# Power_Supply_Section.net
KiCad netlist of a schematic drawn in Altium Designer
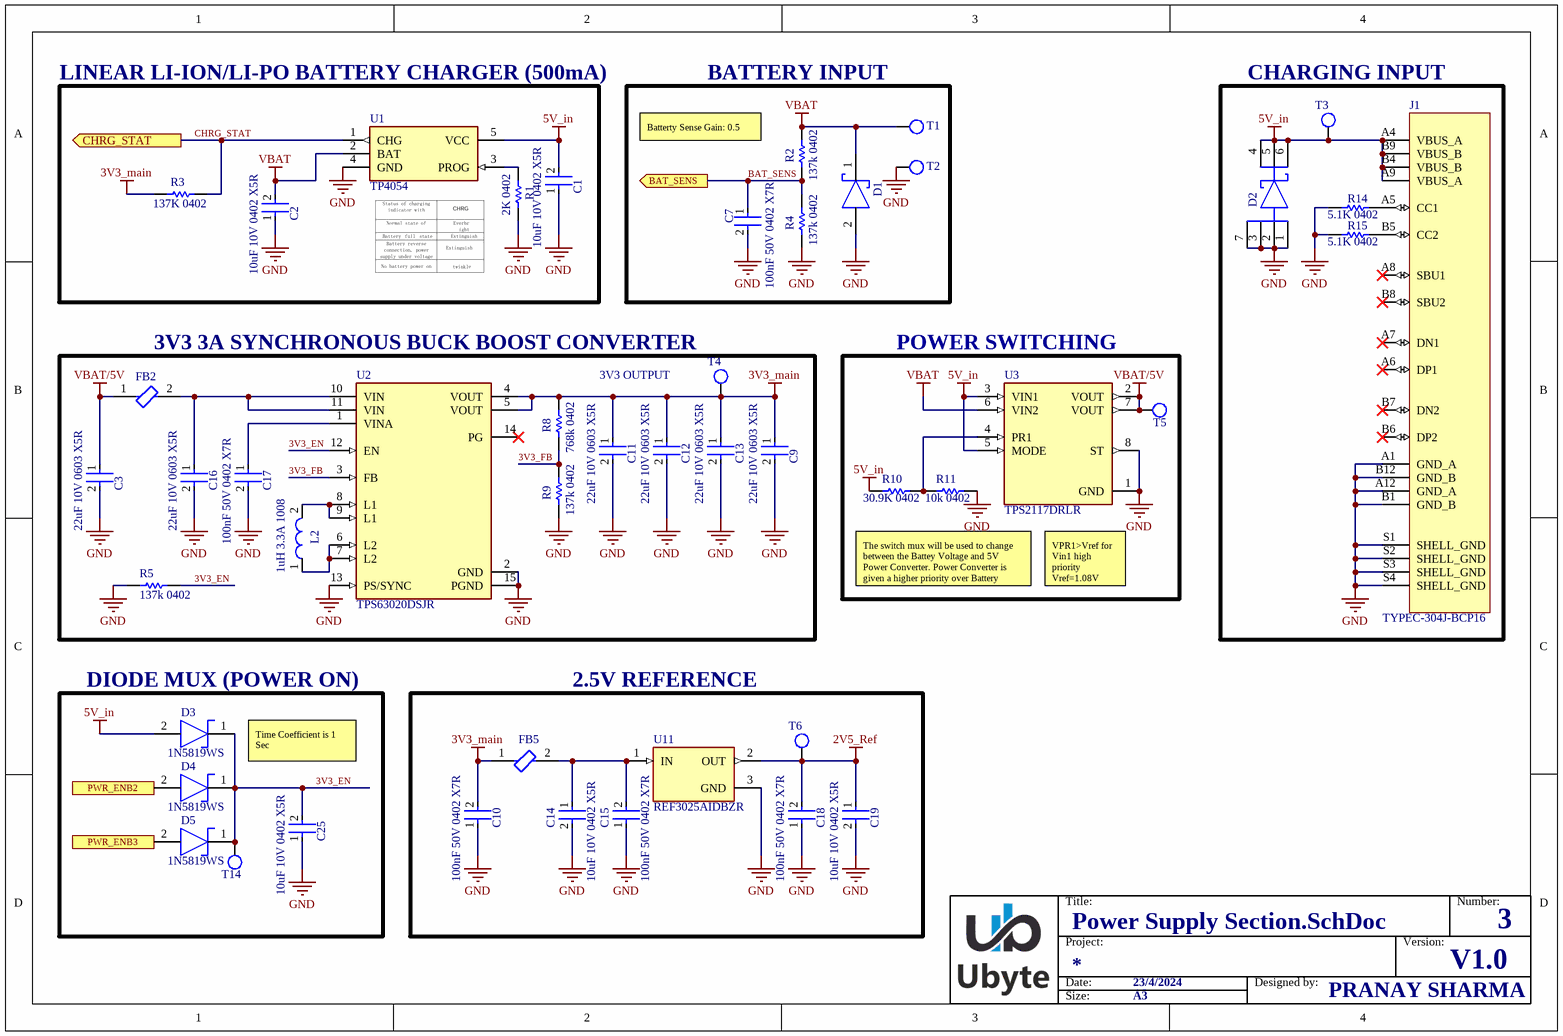
[diagram p0: Power Supply Section.SchDoc]

(export (version "E")
  (design (tool "Eeschema 10.0.6"))
  (components
    (comp (ref "C1")
      (value "10uF 10V 0402 X5R")
      (footprint "Res, Cap, Ind, LED, FB_Lib:0402 IPC CLASS C CAPACITOR")
      (libsource (lib "Capacitor_Lib") (part "10uF 10V 0402 X5R"))
    )
    (comp (ref "C2")
      (value "10uF 10V 0402 X5R")
      (footprint "Res, Cap, Ind, LED, FB_Lib:0402 IPC CLASS C CAPACITOR")
      (libsource (lib "Capacitor_Lib") (part "10uF 10V 0402 X5R"))
    )
    (comp (ref "C3")
      (value "22uF 10V 0603 X5R")
      (footprint "Res, Cap, Ind, LED, FB_Lib:0603 IPC CLASS C CAPACITOR")
      (libsource (lib "Capacitor_Lib") (part "22uF 10V 0603 X5R"))
    )
    (comp (ref "C7")
      (value "100nF 50V 0402 X7R")
      (footprint "Res, Cap, Ind, LED, FB_Lib:0402 IPC CLASS C CAPACITOR")
      (libsource (lib "Capacitor_Lib") (part "100nF 50V 0402 X7R"))
    )
    (comp (ref "C9")
      (value "22uF 10V 0603 X5R")
      (footprint "Res, Cap, Ind, LED, FB_Lib:0603 IPC CLASS C CAPACITOR")
      (libsource (lib "Capacitor_Lib") (part "22uF 10V 0603 X5R"))
    )
    (comp (ref "C10")
      (value "100nF 50V 0402 X7R")
      (footprint "Res, Cap, Ind, LED, FB_Lib:0402 IPC CLASS C CAPACITOR")
      (libsource (lib "Capacitor_Lib") (part "100nF 50V 0402 X7R"))
    )
    (comp (ref "C11")
      (value "22uF 10V 0603 X5R")
      (footprint "Res, Cap, Ind, LED, FB_Lib:0603 IPC CLASS C CAPACITOR")
      (libsource (lib "Capacitor_Lib") (part "22uF 10V 0603 X5R"))
    )
    (comp (ref "C12")
      (value "22uF 10V 0603 X5R")
      (footprint "Res, Cap, Ind, LED, FB_Lib:0603 IPC CLASS C CAPACITOR")
      (libsource (lib "Capacitor_Lib") (part "22uF 10V 0603 X5R"))
    )
    (comp (ref "C13")
      (value "22uF 10V 0603 X5R")
      (footprint "Res, Cap, Ind, LED, FB_Lib:0603 IPC CLASS C CAPACITOR")
      (libsource (lib "Capacitor_Lib") (part "22uF 10V 0603 X5R"))
    )
    (comp (ref "C14")
      (value "10uF 10V 0402 X5R")
      (footprint "Res, Cap, Ind, LED, FB_Lib:0402 IPC CLASS C CAPACITOR")
      (libsource (lib "Capacitor_Lib") (part "10uF 10V 0402 X5R"))
    )
    (comp (ref "C15")
      (value "100nF 50V 0402 X7R")
      (footprint "Res, Cap, Ind, LED, FB_Lib:0402 IPC CLASS C CAPACITOR")
      (libsource (lib "Capacitor_Lib") (part "100nF 50V 0402 X7R"))
    )
    (comp (ref "C16")
      (value "22uF 10V 0603 X5R")
      (footprint "Res, Cap, Ind, LED, FB_Lib:0603 IPC CLASS C CAPACITOR")
      (libsource (lib "Capacitor_Lib") (part "22uF 10V 0603 X5R"))
    )
    (comp (ref "C17")
      (value "100nF 50V 0402 X7R")
      (footprint "Res, Cap, Ind, LED, FB_Lib:0402 IPC CLASS C CAPACITOR")
      (libsource (lib "Capacitor_Lib") (part "100nF 50V 0402 X7R"))
    )
    (comp (ref "C18")
      (value "100nF 50V 0402 X7R")
      (footprint "Res, Cap, Ind, LED, FB_Lib:0402 IPC CLASS C CAPACITOR")
      (libsource (lib "Capacitor_Lib") (part "100nF 50V 0402 X7R"))
    )
    (comp (ref "C19")
      (value "10uF 10V 0402 X5R")
      (footprint "Res, Cap, Ind, LED, FB_Lib:0402 IPC CLASS C CAPACITOR")
      (libsource (lib "Capacitor_Lib") (part "10uF 10V 0402 X5R"))
    )
    (comp (ref "C25")
      (value "10uF 10V 0402 X5R")
      (footprint "Res, Cap, Ind, LED, FB_Lib:0402 IPC CLASS C CAPACITOR")
      (libsource (lib "Capacitor_Lib") (part "10uF 10V 0402 X5R"))
    )
    (comp (ref "D1")
      (value "SP3031-01ETG")
      (footprint "Res, Cap, Ind, LED, FB_Lib:SOD882 IPC-C")
      (libsource (lib "Diodes_Lib") (part "SP3031-01ETG"))
    )
    (comp (ref "D2")
      (value "TVS0500DRVR")
      (footprint "Res, Cap, Ind, LED, FB_Lib:DRV0006A IPC-C")
      (libsource (lib "Diodes_Lib") (part "TVS0500DRVR"))
    )
    (comp (ref "D3")
      (value "1N5819WS")
      (footprint "Res, Cap, Ind, LED, FB_Lib:SOD-323 IPC-C")
      (libsource (lib "Diodes_Lib") (part "1N5819WS"))
    )
    (comp (ref "D4")
      (value "1N5819WS")
      (footprint "Res, Cap, Ind, LED, FB_Lib:SOD-323 IPC-C")
      (libsource (lib "Diodes_Lib") (part "1N5819WS"))
    )
    (comp (ref "D5")
      (value "1N5819WS")
      (footprint "Res, Cap, Ind, LED, FB_Lib:SOD-323 IPC-C")
      (libsource (lib "Diodes_Lib") (part "1N5819WS"))
    )
    (comp (ref "FB2")
      (value "BLM21SP111SN1D")
      (footprint "Res, Cap, Ind, LED, FB_Lib:0603 IPC CLASS C FERRITE BEAD")
      (libsource (lib "Ferrite_Bead_Lib") (part "BLM21SP111SN1D"))
    )
    (comp (ref "FB5")
      (value "BLM15AX102SN1D")
      (footprint "Res, Cap, Ind, LED, FB_Lib:0402 IPC CLASS C FERRITE BEAD")
      (libsource (lib "Ferrite_Bead_Lib") (part "BLM15AX102SN1D"))
    )
    (comp (ref "J1")
      (value "TYPEC-304J-BCP16")
      (footprint "VALCON_CSP-USC16-TR")
      (libsource (lib "V1.0") (part "USB Type C"))
    )
    (comp (ref "L2")
      (value "1uH 3.3A 1008")
      (footprint "Res, Cap, Ind, LED, FB_Lib:1008 Inductor IPC-C")
      (libsource (lib "Inductor_Lib") (part "DFE252012F-1R0M=P2"))
    )
    (comp (ref "R1")
      (value "2K 0402")
      (footprint "Res, Cap, Ind, LED, FB_Lib:0402 IPC CLASS C RESISTOR")
      (libsource (lib "Resistor_Lib") (part "2K 1% 0402"))
    )
    (comp (ref "R2")
      (value "137k 0402")
      (footprint "Res, Cap, Ind, LED, FB_Lib:0402 IPC CLASS C RESISTOR")
      (libsource (lib "Resistor_Lib") (part "10k 1% 0402"))
    )
    (comp (ref "R3")
      (value "137K 0402")
      (footprint "Res, Cap, Ind, LED, FB_Lib:0402 IPC CLASS C RESISTOR")
      (libsource (lib "Resistor_Lib") (part "137K 1% 0402"))
    )
    (comp (ref "R4")
      (value "137k 0402")
      (footprint "Res, Cap, Ind, LED, FB_Lib:0402 IPC CLASS C RESISTOR")
      (libsource (lib "Resistor_Lib") (part "10k 1% 0402"))
    )
    (comp (ref "R5")
      (value "137k 0402")
      (footprint "Res, Cap, Ind, LED, FB_Lib:0402 IPC CLASS C RESISTOR")
      (libsource (lib "Resistor_Lib") (part "10k 1% 0402"))
    )
    (comp (ref "R8")
      (value "768k 0402")
      (footprint "Res, Cap, Ind, LED, FB_Lib:0402 IPC CLASS C RESISTOR")
      (libsource (lib "Resistor_Lib") (part "10k 1% 0402"))
    )
    (comp (ref "R9")
      (value "137k 0402")
      (footprint "Res, Cap, Ind, LED, FB_Lib:0402 IPC CLASS C RESISTOR")
      (libsource (lib "Resistor_Lib") (part "10k 1% 0402"))
    )
    (comp (ref "R10")
      (value "30.9K 0402")
      (footprint "Res, Cap, Ind, LED, FB_Lib:0402 IPC CLASS C RESISTOR")
      (libsource (lib "Resistor_Lib") (part "30.9K 1%  0402"))
    )
    (comp (ref "R11")
      (value "10k 0402")
      (footprint "Res, Cap, Ind, LED, FB_Lib:0402 IPC CLASS C RESISTOR")
      (libsource (lib "Resistor_Lib") (part "10k 1% 0402"))
    )
    (comp (ref "R14")
      (value "5.1K 0402")
      (footprint "Res, Cap, Ind, LED, FB_Lib:0402 IPC CLASS C RESISTOR")
      (libsource (lib "Resistor_Lib") (part "5.1K 1% 0402"))
    )
    (comp (ref "R15")
      (value "5.1K 0402")
      (footprint "Res, Cap, Ind, LED, FB_Lib:0402 IPC CLASS C RESISTOR")
      (libsource (lib "Resistor_Lib") (part "5.1K 1% 0402"))
    )
    (comp (ref "T1")
      (value "Test Point TH")
      (footprint "Miscellaneous_Lib:Test Point TH")
      (libsource (lib "Miscellaneous_Lib") (part "Test Point TH"))
    )
    (comp (ref "T2")
      (value "Test Point TH")
      (footprint "Miscellaneous_Lib:Test Point TH")
      (libsource (lib "Miscellaneous_Lib") (part "Test Point TH"))
    )
    (comp (ref "T3")
      (value "TP")
      (footprint "Miscellaneous_Lib:Testpoint1")
      (libsource (lib "Miscellaneous_Lib") (part "Testpoint1"))
    )
    (comp (ref "T4")
      (value "TP")
      (footprint "Miscellaneous_Lib:Testpoint1")
      (libsource (lib "Miscellaneous_Lib") (part "Testpoint1"))
    )
    (comp (ref "T5")
      (value "TP")
      (footprint "Miscellaneous_Lib:Testpoint1")
      (libsource (lib "Miscellaneous_Lib") (part "Testpoint1"))
    )
    (comp (ref "T6")
      (value "TP")
      (footprint "Miscellaneous_Lib:Testpoint1")
      (libsource (lib "Miscellaneous_Lib") (part "Testpoint1"))
    )
    (comp (ref "T14")
      (value "TP")
      (footprint "Miscellaneous_Lib:Testpoint1")
      (libsource (lib "Miscellaneous_Lib") (part "Testpoint1"))
    )
    (comp (ref "U1")
      (value "TP4054")
      (footprint "Integrated_Circuits_Lib:DBV0005A IPC-C")
      (libsource (lib "Integrated_Circuits_Lib") (part "TP4054"))
    )
    (comp (ref "U2")
      (value "TPS63020DSJR")
      (footprint "FP-DSJ0014A-MFG")
      (libsource (lib "Altium Content Vault") (part "ca84f4b88d1e031d86a58c77b9c066d"))
    )
    (comp (ref "U3")
      (value "TPS2117DRLR")
      (footprint "Integrated_Circuits_Lib:DRL0008A IPC-C")
      (libsource (lib "Integrated_Circuits_Lib") (part "TPS2117DRLR"))
    )
    (comp (ref "U11")
      (value "REF3025AIDBZR")
      (footprint "Integrated_Circuits_Lib:SOT23-IPC_C")
      (libsource (lib "Integrated_Circuits_Lib") (part "REF3025AIDBZR"))
    )
  )
  (nets
    (net (code "1") (name "/3V3_EN") (class "Default")
      (node (ref "C25") (pin "2") (pinfunction "2_2") (pintype "passive"))
      (node (ref "D3") (pin "1") (pinfunction "C_1") (pintype "passive"))
      (node (ref "D4") (pin "1") (pinfunction "C_1") (pintype "passive"))
      (node (ref "D5") (pin "1") (pinfunction "C_1") (pintype "passive"))
      (node (ref "R5") (pin "1") (pinfunction "1_1") (pintype "passive"))
      (node (ref "T14") (pin "0") (pinfunction "0_0") (pintype "passive"))
      (node (ref "U2") (pin "12") (pinfunction "EN_12") (pintype "input"))
    )
    (net (code "2") (name "/3V3_FB") (class "Default")
      (node (ref "R8") (pin "2") (pinfunction "2_2") (pintype "passive"))
      (node (ref "R9") (pin "2") (pinfunction "2_2") (pintype "passive"))
      (node (ref "U2") (pin "3") (pinfunction "FB_3") (pintype "input"))
    )
    (net (code "3") (name "/BAT_SENS") (class "Default")
      (node (ref "C7") (pin "1") (pinfunction "1_1") (pintype "passive"))
      (node (ref "R2") (pin "1") (pinfunction "1_1") (pintype "passive"))
      (node (ref "R4") (pin "2") (pinfunction "2_2") (pintype "passive"))
    )
    (net (code "4") (name "/CHRG_STAT") (class "Default")
      (node (ref "R3") (pin "2") (pinfunction "2_2") (pintype "passive"))
      (node (ref "U1") (pin "1") (pinfunction "CHG_1") (pintype "output"))
    )
    (net (code "5") (name "/PWR_ENB2") (class "Default")
      (node (ref "D4") (pin "2") (pinfunction "A_2") (pintype "passive"))
    )
    (net (code "6") (name "/PWR_ENB3") (class "Default")
      (node (ref "D5") (pin "2") (pinfunction "A_2") (pintype "passive"))
    )
    (net (code "7") (name "2V5_Ref") (class "Default")
      (node (ref "C18") (pin "2") (pinfunction "2_2") (pintype "passive"))
      (node (ref "C19") (pin "1") (pinfunction "1_1") (pintype "passive"))
      (node (ref "T6") (pin "0") (pinfunction "0_0") (pintype "passive"))
      (node (ref "U11") (pin "2") (pinfunction "OUT_2") (pintype "output"))
    )
    (net (code "8") (name "3V3_main") (class "Default")
      (node (ref "C10") (pin "2") (pinfunction "2_2") (pintype "passive"))
      (node (ref "C11") (pin "1") (pinfunction "1_1") (pintype "passive"))
      (node (ref "C12") (pin "1") (pinfunction "1_1") (pintype "passive"))
      (node (ref "C13") (pin "1") (pinfunction "1_1") (pintype "passive"))
      (node (ref "C9") (pin "1") (pinfunction "1_1") (pintype "passive"))
      (node (ref "FB5") (pin "1") (pinfunction "1_1") (pintype "passive"))
      (node (ref "R3") (pin "1") (pinfunction "1_1") (pintype "passive"))
      (node (ref "R8") (pin "1") (pinfunction "1_1") (pintype "passive"))
      (node (ref "T4") (pin "0") (pinfunction "0_0") (pintype "passive"))
      (node (ref "U2") (pin "4") (pinfunction "VOUT_4") (pintype "power_in"))
      (node (ref "U2") (pin "5") (pinfunction "VOUT_5") (pintype "power_in"))
    )
    (net (code "9") (name "5V_in") (class "Default")
      (node (ref "C1") (pin "2") (pinfunction "2_2") (pintype "passive"))
      (node (ref "D2") (pin "4") (pinfunction "4_4") (pintype "passive"))
      (node (ref "D2") (pin "5") (pinfunction "5_5") (pintype "passive"))
      (node (ref "D2") (pin "6") (pinfunction "6_6") (pintype "passive"))
      (node (ref "D3") (pin "2") (pinfunction "A_2") (pintype "passive"))
      (node (ref "J1") (pin "A4") (pinfunction "VBUS_A_A4") (pintype "power_in"))
      (node (ref "J1") (pin "A9") (pinfunction "VBUS_A_A9") (pintype "power_in"))
      (node (ref "J1") (pin "B4") (pinfunction "VBUS_B_B4") (pintype "power_in"))
      (node (ref "J1") (pin "B9") (pinfunction "VBUS_B_B9") (pintype "power_in"))
      (node (ref "R10") (pin "2") (pinfunction "2_2") (pintype "passive"))
      (node (ref "T3") (pin "0") (pinfunction "0_0") (pintype "passive"))
      (node (ref "U1") (pin "5") (pinfunction "VCC_5") (pintype "power_in"))
      (node (ref "U3") (pin "3") (pinfunction "VIN1_3") (pintype "input"))
      (node (ref "U3") (pin "5") (pinfunction "MODE_5") (pintype "input"))
    )
    (net (code "10") (name "GND") (class "Default")
      (node (ref "C1") (pin "1") (pinfunction "1_1") (pintype "passive"))
      (node (ref "C10") (pin "1") (pinfunction "1_1") (pintype "passive"))
      (node (ref "C11") (pin "2") (pinfunction "2_2") (pintype "passive"))
      (node (ref "C12") (pin "2") (pinfunction "2_2") (pintype "passive"))
      (node (ref "C13") (pin "2") (pinfunction "2_2") (pintype "passive"))
      (node (ref "C14") (pin "2") (pinfunction "2_2") (pintype "passive"))
      (node (ref "C15") (pin "1") (pinfunction "1_1") (pintype "passive"))
      (node (ref "C16") (pin "2") (pinfunction "2_2") (pintype "passive"))
      (node (ref "C17") (pin "2") (pinfunction "2_2") (pintype "passive"))
      (node (ref "C18") (pin "1") (pinfunction "1_1") (pintype "passive"))
      (node (ref "C19") (pin "2") (pinfunction "2_2") (pintype "passive"))
      (node (ref "C2") (pin "1") (pinfunction "1_1") (pintype "passive"))
      (node (ref "C25") (pin "1") (pinfunction "1_1") (pintype "passive"))
      (node (ref "C3") (pin "2") (pinfunction "2_2") (pintype "passive"))
      (node (ref "C7") (pin "2") (pinfunction "2_2") (pintype "passive"))
      (node (ref "C9") (pin "2") (pinfunction "2_2") (pintype "passive"))
      (node (ref "D1") (pin "2") (pinfunction "A_2") (pintype "passive"))
      (node (ref "D2") (pin "1") (pinfunction "C_1") (pintype "passive"))
      (node (ref "D2") (pin "2") (pinfunction "A_2") (pintype "passive"))
      (node (ref "D2") (pin "3") (pinfunction "3_3") (pintype "passive"))
      (node (ref "D2") (pin "7") (pinfunction "7_7") (pintype "passive"))
      (node (ref "J1") (pin "A1") (pinfunction "GND_A_A1") (pintype "power_in"))
      (node (ref "J1") (pin "A12") (pinfunction "GND_A_A12") (pintype "power_in"))
      (node (ref "J1") (pin "B1") (pinfunction "GND_B_B1") (pintype "power_in"))
      (node (ref "J1") (pin "B12") (pinfunction "GND_B_B12") (pintype "power_in"))
      (node (ref "J1") (pin "S1") (pinfunction "SHELL_GND_S1") (pintype "power_in"))
      (node (ref "J1") (pin "S2") (pinfunction "SHELL_GND_S2") (pintype "power_in"))
      (node (ref "J1") (pin "S3") (pinfunction "SHELL_GND_S3") (pintype "power_in"))
      (node (ref "J1") (pin "S4") (pinfunction "SHELL_GND_S4") (pintype "power_in"))
      (node (ref "R1") (pin "2") (pinfunction "2_2") (pintype "passive"))
      (node (ref "R11") (pin "1") (pinfunction "1_1") (pintype "passive"))
      (node (ref "R14") (pin "1") (pinfunction "1_1") (pintype "passive"))
      (node (ref "R15") (pin "1") (pinfunction "1_1") (pintype "passive"))
      (node (ref "R4") (pin "1") (pinfunction "1_1") (pintype "passive"))
      (node (ref "R5") (pin "2") (pinfunction "2_2") (pintype "passive"))
      (node (ref "R9") (pin "1") (pinfunction "1_1") (pintype "passive"))
      (node (ref "T2") (pin "0") (pinfunction "0_0") (pintype "passive"))
      (node (ref "U1") (pin "4") (pinfunction "GND_4") (pintype "power_in"))
      (node (ref "U11") (pin "3") (pinfunction "GND_3") (pintype "power_in"))
      (node (ref "U2") (pin "13") (pinfunction "PS/SYNC_13") (pintype "input"))
      (node (ref "U2") (pin "15") (pinfunction "PGND_15") (pintype "power_in"))
      (node (ref "U2") (pin "2") (pinfunction "GND_2") (pintype "power_in"))
      (node (ref "U3") (pin "1") (pinfunction "GND_1") (pintype "power_in"))
      (node (ref "U3") (pin "8") (pinfunction "ST_8") (pintype "output"))
    )
    (net (code "11") (name "Net-(C16-Pad1)") (class "Default")
      (node (ref "C16") (pin "1") (pinfunction "1_1") (pintype "passive"))
      (node (ref "FB2") (pin "2") (pinfunction "2_2") (pintype "passive"))
      (node (ref "U2") (pin "10") (pinfunction "VIN_10") (pintype "power_in"))
      (node (ref "U2") (pin "11") (pinfunction "VIN_11") (pintype "power_in"))
    )
    (net (code "12") (name "Net-(J1-CC1)") (class "Default")
      (node (ref "J1") (pin "A5") (pinfunction "CC1_A5") (pintype "bidirectional"))
      (node (ref "R14") (pin "2") (pinfunction "2_2") (pintype "passive"))
    )
    (net (code "13") (name "Net-(J1-CC2)") (class "Default")
      (node (ref "J1") (pin "B5") (pinfunction "CC2_B5") (pintype "bidirectional"))
      (node (ref "R15") (pin "2") (pinfunction "2_2") (pintype "passive"))
    )
    (net (code "14") (name "Net-(L2-Pad1)") (class "Default")
      (node (ref "L2") (pin "1") (pinfunction "1_1") (pintype "passive"))
      (node (ref "U2") (pin "6") (pinfunction "L2_6") (pintype "input"))
      (node (ref "U2") (pin "7") (pinfunction "L2_7") (pintype "input"))
    )
    (net (code "15") (name "Net-(L2-Pad2)") (class "Default")
      (node (ref "L2") (pin "2") (pinfunction "2_2") (pintype "passive"))
      (node (ref "U2") (pin "8") (pinfunction "L1_8") (pintype "input"))
      (node (ref "U2") (pin "9") (pinfunction "L1_9") (pintype "input"))
    )
    (net (code "16") (name "Net-(U1-PROG)") (class "Default")
      (node (ref "R1") (pin "1") (pinfunction "1_1") (pintype "passive"))
      (node (ref "U1") (pin "3") (pinfunction "PROG_3") (pintype "input"))
    )
    (net (code "17") (name "Net-(U2-VINA)") (class "Default")
      (node (ref "C17") (pin "1") (pinfunction "1_1") (pintype "passive"))
      (node (ref "U2") (pin "1") (pinfunction "VINA_1") (pintype "power_in"))
    )
    (net (code "18") (name "Net-(U3-PR1)") (class "Default")
      (node (ref "R10") (pin "1") (pinfunction "1_1") (pintype "passive"))
      (node (ref "R11") (pin "2") (pinfunction "2_2") (pintype "passive"))
      (node (ref "U3") (pin "4") (pinfunction "PR1_4") (pintype "input"))
    )
    (net (code "19") (name "Net-(U11-IN)") (class "Default")
      (node (ref "C14") (pin "1") (pinfunction "1_1") (pintype "passive"))
      (node (ref "C15") (pin "2") (pinfunction "2_2") (pintype "passive"))
      (node (ref "FB5") (pin "2") (pinfunction "2_2") (pintype "passive"))
      (node (ref "U11") (pin "1") (pinfunction "IN_1") (pintype "input"))
    )
    (net (code "20") (name "VBAT") (class "Default")
      (node (ref "C2") (pin "2") (pinfunction "2_2") (pintype "passive"))
      (node (ref "D1") (pin "1") (pinfunction "C_1") (pintype "passive"))
      (node (ref "R2") (pin "2") (pinfunction "2_2") (pintype "passive"))
      (node (ref "T1") (pin "0") (pinfunction "0_0") (pintype "passive"))
      (node (ref "U1") (pin "2") (pinfunction "BAT_2") (pintype "power_in"))
      (node (ref "U3") (pin "6") (pinfunction "VIN2_6") (pintype "input"))
    )
    (net (code "21") (name "VBAT{slash}5V") (class "Default")
      (node (ref "C3") (pin "1") (pinfunction "1_1") (pintype "passive"))
      (node (ref "FB2") (pin "1") (pinfunction "1_1") (pintype "passive"))
      (node (ref "T5") (pin "0") (pinfunction "0_0") (pintype "passive"))
      (node (ref "U3") (pin "2") (pinfunction "VOUT_2") (pintype "output"))
      (node (ref "U3") (pin "7") (pinfunction "VOUT_7") (pintype "output"))
    )
    (net (code "22") (name "unconnected-(J1-DN1-PadA7)") (class "Default")
      (node (ref "J1") (pin "A7") (pinfunction "DN1_A7") (pintype "bidirectional+no_connect"))
    )
    (net (code "23") (name "unconnected-(J1-DN2-PadB7)") (class "Default")
      (node (ref "J1") (pin "B7") (pinfunction "DN2_B7") (pintype "bidirectional+no_connect"))
    )
    (net (code "24") (name "unconnected-(J1-DP1-PadA6)") (class "Default")
      (node (ref "J1") (pin "A6") (pinfunction "DP1_A6") (pintype "bidirectional+no_connect"))
    )
    (net (code "25") (name "unconnected-(J1-DP2-PadB6)") (class "Default")
      (node (ref "J1") (pin "B6") (pinfunction "DP2_B6") (pintype "bidirectional+no_connect"))
    )
    (net (code "26") (name "unconnected-(J1-SBU1-PadA8)") (class "Default")
      (node (ref "J1") (pin "A8") (pinfunction "SBU1_A8") (pintype "bidirectional+no_connect"))
    )
    (net (code "27") (name "unconnected-(J1-SBU2-PadB8)") (class "Default")
      (node (ref "J1") (pin "B8") (pinfunction "SBU2_B8") (pintype "bidirectional+no_connect"))
    )
    (net (code "28") (name "unconnected-(U2-PG-Pad14)") (class "Default")
      (node (ref "U2") (pin "14") (pinfunction "PG_14") (pintype "open_collector+no_connect"))
    )
  )
)
